# INPUT.net
KiCad netlist of a schematic drawn in Altium Designer
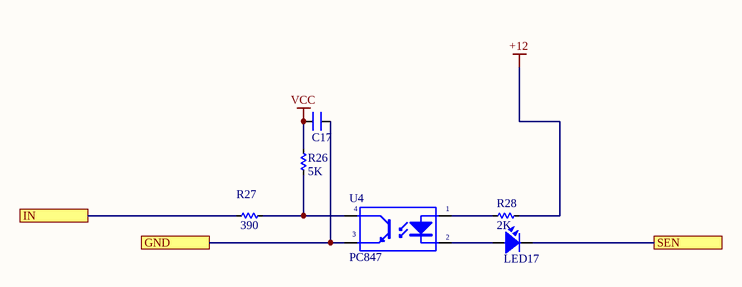
[diagram p0: INPUT.SchDoc]

(export (version "E")
  (design (tool "Eeschema 10.0.6"))
  (components
    (comp (ref "C17") (value "CN") (footprint "CN-SMD-0603_big") (libsource (lib "nhan") (part "CN")))
    (comp (ref "LED17")
      (value "LED")
      (footprint "LED-0805-Green")
      (libsource (lib "BanLinhKien") (part "LED SMD"))
    )
    (comp (ref "R26") (value "5K") (footprint "RES-SMD-0603_BIG") (libsource (lib "nhan") (part "R")))
    (comp (ref "R27") (value "390") (footprint "RES-SMD-0603_BIG") (libsource (lib "nhan") (part "R")))
    (comp (ref "R28") (value "2K") (footprint "RES-SMD-0603_BIG") (libsource (lib "nhan") (part "R")))
    (comp (ref "U4")
      (value "PC847")
      (footprint "DIP4")
      (description "Single Opto")
      (libsource (lib "BanLinhKien") (part "PC817"))
    )
  )
  (nets
    (net (code "1") (name "+12") (class "Default")
      (node (ref "R28") (pin "1") (pinfunction "1_1") (pintype "passive"))
    )
    (net (code "2") (name "/GND") (class "Default")
      (node (ref "C17") (pin "2") (pinfunction "2_2") (pintype "passive"))
      (node (ref "U4") (pin "3") (pinfunction "E_3") (pintype "passive"))
    )
    (net (code "3") (name "/IN") (class "Default")
      (node (ref "R27") (pin "1") (pinfunction "1_1") (pintype "passive"))
    )
    (net (code "4") (name "/SEN") (class "Default")
      (node (ref "LED17") (pin "2") (pinfunction "2_2") (pintype "passive"))
    )
    (net (code "5") (name "Net-(U4-A)") (class "Default")
      (node (ref "R28") (pin "2") (pinfunction "2_2") (pintype "passive"))
      (node (ref "U4") (pin "1") (pinfunction "A_1") (pintype "passive"))
    )
    (net (code "6") (name "Net-(U4-C)") (class "Default")
      (node (ref "R26") (pin "2") (pinfunction "2_2") (pintype "passive"))
      (node (ref "R27") (pin "2") (pinfunction "2_2") (pintype "passive"))
      (node (ref "U4") (pin "4") (pinfunction "C_4") (pintype "passive"))
    )
    (net (code "7") (name "Net-(U4-K)") (class "Default")
      (node (ref "LED17") (pin "1") (pinfunction "1_1") (pintype "passive"))
      (node (ref "U4") (pin "2") (pinfunction "K_2") (pintype "passive"))
    )
    (net (code "8") (name "VCC") (class "Default")
      (node (ref "C17") (pin "1") (pinfunction "1_1") (pintype "passive"))
      (node (ref "R26") (pin "1") (pinfunction "1_1") (pintype "passive"))
    )
  )
)
